# 3V3-CAN.net
KiCad netlist of a schematic drawn in Altium Designer
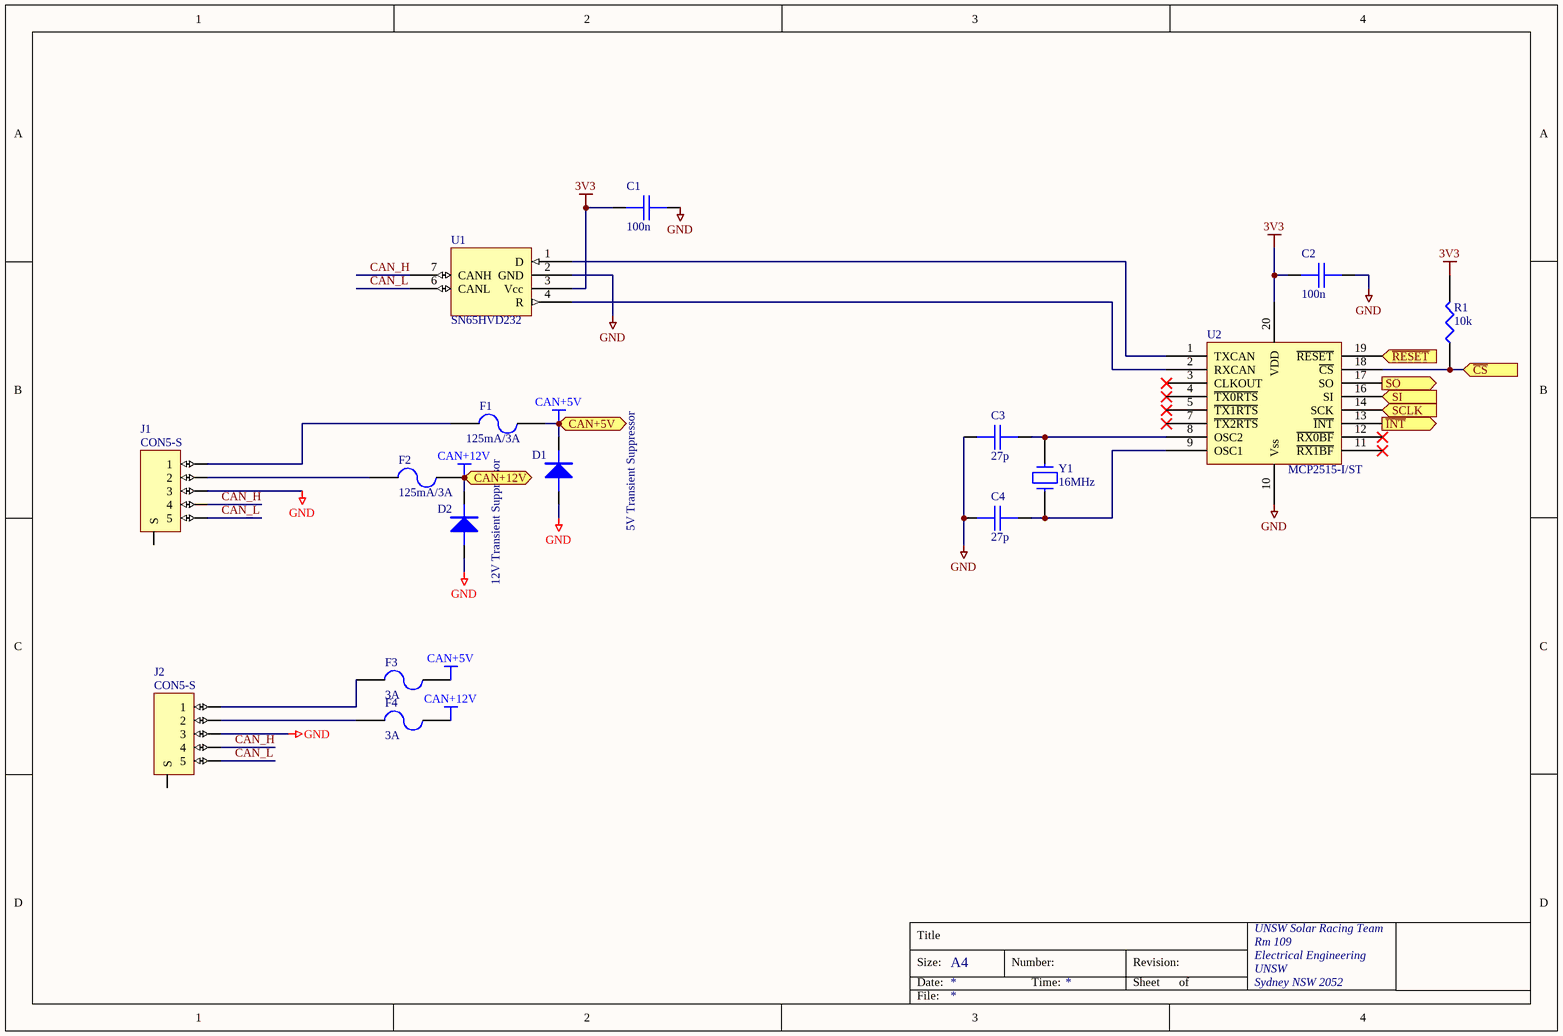
[diagram p0: 3V3-CAN.SchDoc]

(export (version "E")
  (design (tool "Eeschema 10.0.6"))
  (components
    (comp (ref "C1")
      (value "100n")
      (footprint "0603")
      (description "Capacitor")
      (libsource (lib "*") (part "CAP"))
    )
    (comp (ref "C2")
      (value "100n")
      (footprint "0603")
      (description "Capacitor")
      (libsource (lib "*") (part "CAP"))
    )
    (comp (ref "C3")
      (value "27p")
      (footprint "0603")
      (description "Capacitor")
      (libsource (lib "*") (part "CAP"))
    )
    (comp (ref "C4")
      (value "27p")
      (footprint "0603")
      (description "Capacitor")
      (libsource (lib "*") (part "CAP"))
    )
    (comp (ref "D1")
      (value "5V Transient Suppressor")
      (footprint "SMA")
      (description "Diode")
      (libsource (lib "RCLDQ") (part "DIODE"))
    )
    (comp (ref "D2")
      (value "12V Transient Suppressor")
      (footprint "SMA")
      (description "Diode")
      (libsource (lib "RCLDQ") (part "DIODE"))
    )
    (comp (ref "F1")
      (value "125mA/3A")
      (footprint "LITTELFUSE-154")
      (description "Fuse")
      (libsource (lib "*") (part "FUSE2"))
    )
    (comp (ref "F2")
      (value "125mA/3A")
      (footprint "LITTELFUSE-154")
      (description "Fuse")
      (libsource (lib "*") (part "FUSE2"))
    )
    (comp (ref "F3")
      (value "3A")
      (footprint "LITTELFUSE-154")
      (description "Fuse")
      (libsource (lib "*") (part "FUSE2"))
    )
    (comp (ref "F4")
      (value "3A")
      (footprint "LITTELFUSE-154")
      (description "Fuse")
      (libsource (lib "*") (part "FUSE2"))
    )
    (comp (ref "J1")
      (value "CON5-S")
      (footprint "TRIAD5F")
      (description "Connector, 2 pin, with shield @ S")
      (libsource (lib "*") (part "CON5-S"))
    )
    (comp (ref "J2")
      (value "CON5-S")
      (footprint "TRIAD5F")
      (description "Connector, 2 pin, with shield @ S")
      (libsource (lib "*") (part "CON5-S"))
    )
    (comp (ref "R1") (value "10k") (footprint "0603") (libsource (lib "*") (part "RES1")))
    (comp (ref "U1")
      (value "SN65HVD232")
      (footprint "SO8")
      (description "3.3V CAN Transciever")
      (libsource (lib "*") (part "SN65HVD232"))
    )
    (comp (ref "U2")
      (value "MCP2515-I/ST")
      (footprint "TSSOP20")
      (description "MCP2510 CAN Controller")
      (libsource (lib "CAN") (part "MCP2515X/ST"))
    )
    (comp (ref "Y1")
      (value "16MHz")
      (footprint "HC49/4H")
      (description "Crystal")
      (libsource (lib "*") (part "CRYSTAL"))
    )
  )
  (nets
    (net (code "1") (name "/CAN_H") (class "Default")
      (node (ref "J1") (pin "4") (pinfunction "4_4") (pintype "bidirectional"))
      (node (ref "J2") (pin "4") (pinfunction "4_4") (pintype "bidirectional"))
      (node (ref "U1") (pin "7") (pinfunction "CANH_7") (pintype "bidirectional"))
    )
    (net (code "2") (name "/CAN_L") (class "Default")
      (node (ref "J1") (pin "5") (pinfunction "5_5") (pintype "bidirectional"))
      (node (ref "J2") (pin "5") (pinfunction "5_5") (pintype "bidirectional"))
      (node (ref "U1") (pin "6") (pinfunction "CANL_6") (pintype "bidirectional"))
    )
    (net (code "3") (name "/SCLK") (class "Default")
      (node (ref "U2") (pin "14") (pinfunction "SCK_14") (pintype "passive"))
    )
    (net (code "4") (name "/SI") (class "Default")
      (node (ref "U2") (pin "16") (pinfunction "SI_16") (pintype "passive"))
    )
    (net (code "5") (name "/SO") (class "Default")
      (node (ref "U2") (pin "17") (pinfunction "SO_17") (pintype "passive"))
    )
    (net (code "6") (name "/~{CS}") (class "Default")
      (node (ref "R1") (pin "1") (pinfunction "1_1") (pintype "passive"))
      (node (ref "U2") (pin "18") (pinfunction "~{CS}_18") (pintype "passive"))
    )
    (net (code "7") (name "/~{INT}") (class "Default")
      (node (ref "U2") (pin "13") (pinfunction "~{INT}_13") (pintype "passive"))
    )
    (net (code "8") (name "/~{RESET}") (class "Default")
      (node (ref "U2") (pin "19") (pinfunction "~{RESET}_19") (pintype "passive"))
    )
    (net (code "9") (name "3V3") (class "Default")
      (node (ref "C1") (pin "2") (pinfunction "2_2") (pintype "passive"))
      (node (ref "C2") (pin "1") (pinfunction "1_1") (pintype "passive"))
      (node (ref "R1") (pin "2") (pinfunction "2_2") (pintype "passive"))
      (node (ref "U1") (pin "3") (pinfunction "Vcc_3") (pintype "power_in"))
      (node (ref "U2") (pin "20") (pinfunction "VDD_20") (pintype "passive"))
    )
    (net (code "10") (name "CAN+5V") (class "Default")
      (node (ref "D1") (pin "K") (pinfunction "K_K") (pintype "passive"))
      (node (ref "F1") (pin "2") (pinfunction "2_2") (pintype "passive"))
      (node (ref "F3") (pin "2") (pinfunction "2_2") (pintype "passive"))
    )
    (net (code "11") (name "CAN+12V") (class "Default")
      (node (ref "D2") (pin "K") (pinfunction "K_K") (pintype "passive"))
      (node (ref "F2") (pin "2") (pinfunction "2_2") (pintype "passive"))
      (node (ref "F4") (pin "2") (pinfunction "2_2") (pintype "passive"))
    )
    (net (code "12") (name "GND") (class "Default")
      (node (ref "C1") (pin "1") (pinfunction "1_1") (pintype "passive"))
      (node (ref "C2") (pin "2") (pinfunction "2_2") (pintype "passive"))
      (node (ref "C3") (pin "1") (pinfunction "1_1") (pintype "passive"))
      (node (ref "C4") (pin "1") (pinfunction "1_1") (pintype "passive"))
      (node (ref "D1") (pin "A") (pinfunction "A_A") (pintype "passive"))
      (node (ref "D2") (pin "A") (pinfunction "A_A") (pintype "passive"))
      (node (ref "J1") (pin "3") (pinfunction "3_3") (pintype "bidirectional"))
      (node (ref "J2") (pin "3") (pinfunction "3_3") (pintype "bidirectional"))
      (node (ref "U1") (pin "2") (pinfunction "GND_2") (pintype "power_in"))
      (node (ref "U2") (pin "10") (pinfunction "Vss_10") (pintype "passive"))
    )
    (net (code "13") (name "Net-(F1-Pad1)") (class "Default")
      (node (ref "F1") (pin "1") (pinfunction "1_1") (pintype "passive"))
      (node (ref "J1") (pin "1") (pinfunction "1_1") (pintype "bidirectional"))
    )
    (net (code "14") (name "Net-(F2-Pad1)") (class "Default")
      (node (ref "F2") (pin "1") (pinfunction "1_1") (pintype "passive"))
      (node (ref "J1") (pin "2") (pinfunction "2_2") (pintype "bidirectional"))
    )
    (net (code "15") (name "Net-(F3-Pad1)") (class "Default")
      (node (ref "F3") (pin "1") (pinfunction "1_1") (pintype "passive"))
      (node (ref "J2") (pin "1") (pinfunction "1_1") (pintype "bidirectional"))
    )
    (net (code "16") (name "Net-(F4-Pad1)") (class "Default")
      (node (ref "F4") (pin "1") (pinfunction "1_1") (pintype "passive"))
      (node (ref "J2") (pin "2") (pinfunction "2_2") (pintype "bidirectional"))
    )
    (net (code "17") (name "Net-(U1-D)") (class "Default")
      (node (ref "U1") (pin "1") (pinfunction "D_1") (pintype "input"))
      (node (ref "U2") (pin "1") (pinfunction "TXCAN_1") (pintype "passive"))
    )
    (net (code "18") (name "Net-(U1-R)") (class "Default")
      (node (ref "U1") (pin "4") (pinfunction "R_4") (pintype "output"))
      (node (ref "U2") (pin "2") (pinfunction "RXCAN_2") (pintype "passive"))
    )
    (net (code "19") (name "Net-(U2-OSC1)") (class "Default")
      (node (ref "C4") (pin "2") (pinfunction "2_2") (pintype "passive"))
      (node (ref "U2") (pin "9") (pinfunction "OSC1_9") (pintype "passive"))
      (node (ref "Y1") (pin "2") (pinfunction "2_2") (pintype "passive"))
    )
    (net (code "20") (name "Net-(U2-OSC2)") (class "Default")
      (node (ref "C3") (pin "2") (pinfunction "2_2") (pintype "passive"))
      (node (ref "U2") (pin "8") (pinfunction "OSC2_8") (pintype "passive"))
      (node (ref "Y1") (pin "1") (pinfunction "1_1") (pintype "passive"))
    )
    (net (code "21") (name "unconnected-(J1-S-Pad0)") (class "Default")
      (node (ref "J1") (pin "0") (pinfunction "S_0") (pintype "bidirectional"))
    )
    (net (code "22") (name "unconnected-(J2-S-Pad0)") (class "Default")
      (node (ref "J2") (pin "0") (pinfunction "S_0") (pintype "bidirectional"))
    )
    (net (code "23") (name "unconnected-(U2-CLKOUT-Pad3)") (class "Default")
      (node (ref "U2") (pin "3") (pinfunction "CLKOUT_3") (pintype "passive+no_connect"))
    )
    (net (code "24") (name "unconnected-(U2-~{RX0BF}-Pad12)") (class "Default")
      (node (ref "U2") (pin "12") (pinfunction "~{RX0BF}_12") (pintype "passive+no_connect"))
    )
    (net (code "25") (name "unconnected-(U2-~{RX1BF}-Pad11)") (class "Default")
      (node (ref "U2") (pin "11") (pinfunction "~{RX1BF}_11") (pintype "passive+no_connect"))
    )
    (net (code "26") (name "unconnected-(U2-~{TX0RTS}-Pad4)") (class "Default")
      (node (ref "U2") (pin "4") (pinfunction "~{TX0RTS}_4") (pintype "passive+no_connect"))
    )
    (net (code "27") (name "unconnected-(U2-~{TX1RTS}-Pad5)") (class "Default")
      (node (ref "U2") (pin "5") (pinfunction "~{TX1RTS}_5") (pintype "passive+no_connect"))
    )
    (net (code "28") (name "unconnected-(U2-~{TX2RTS}-Pad7)") (class "Default")
      (node (ref "U2") (pin "7") (pinfunction "~{TX2RTS}_7") (pintype "passive+no_connect"))
    )
  )
)
